# openmotestm.net
KiCad netlist of a schematic drawn in EAGLE
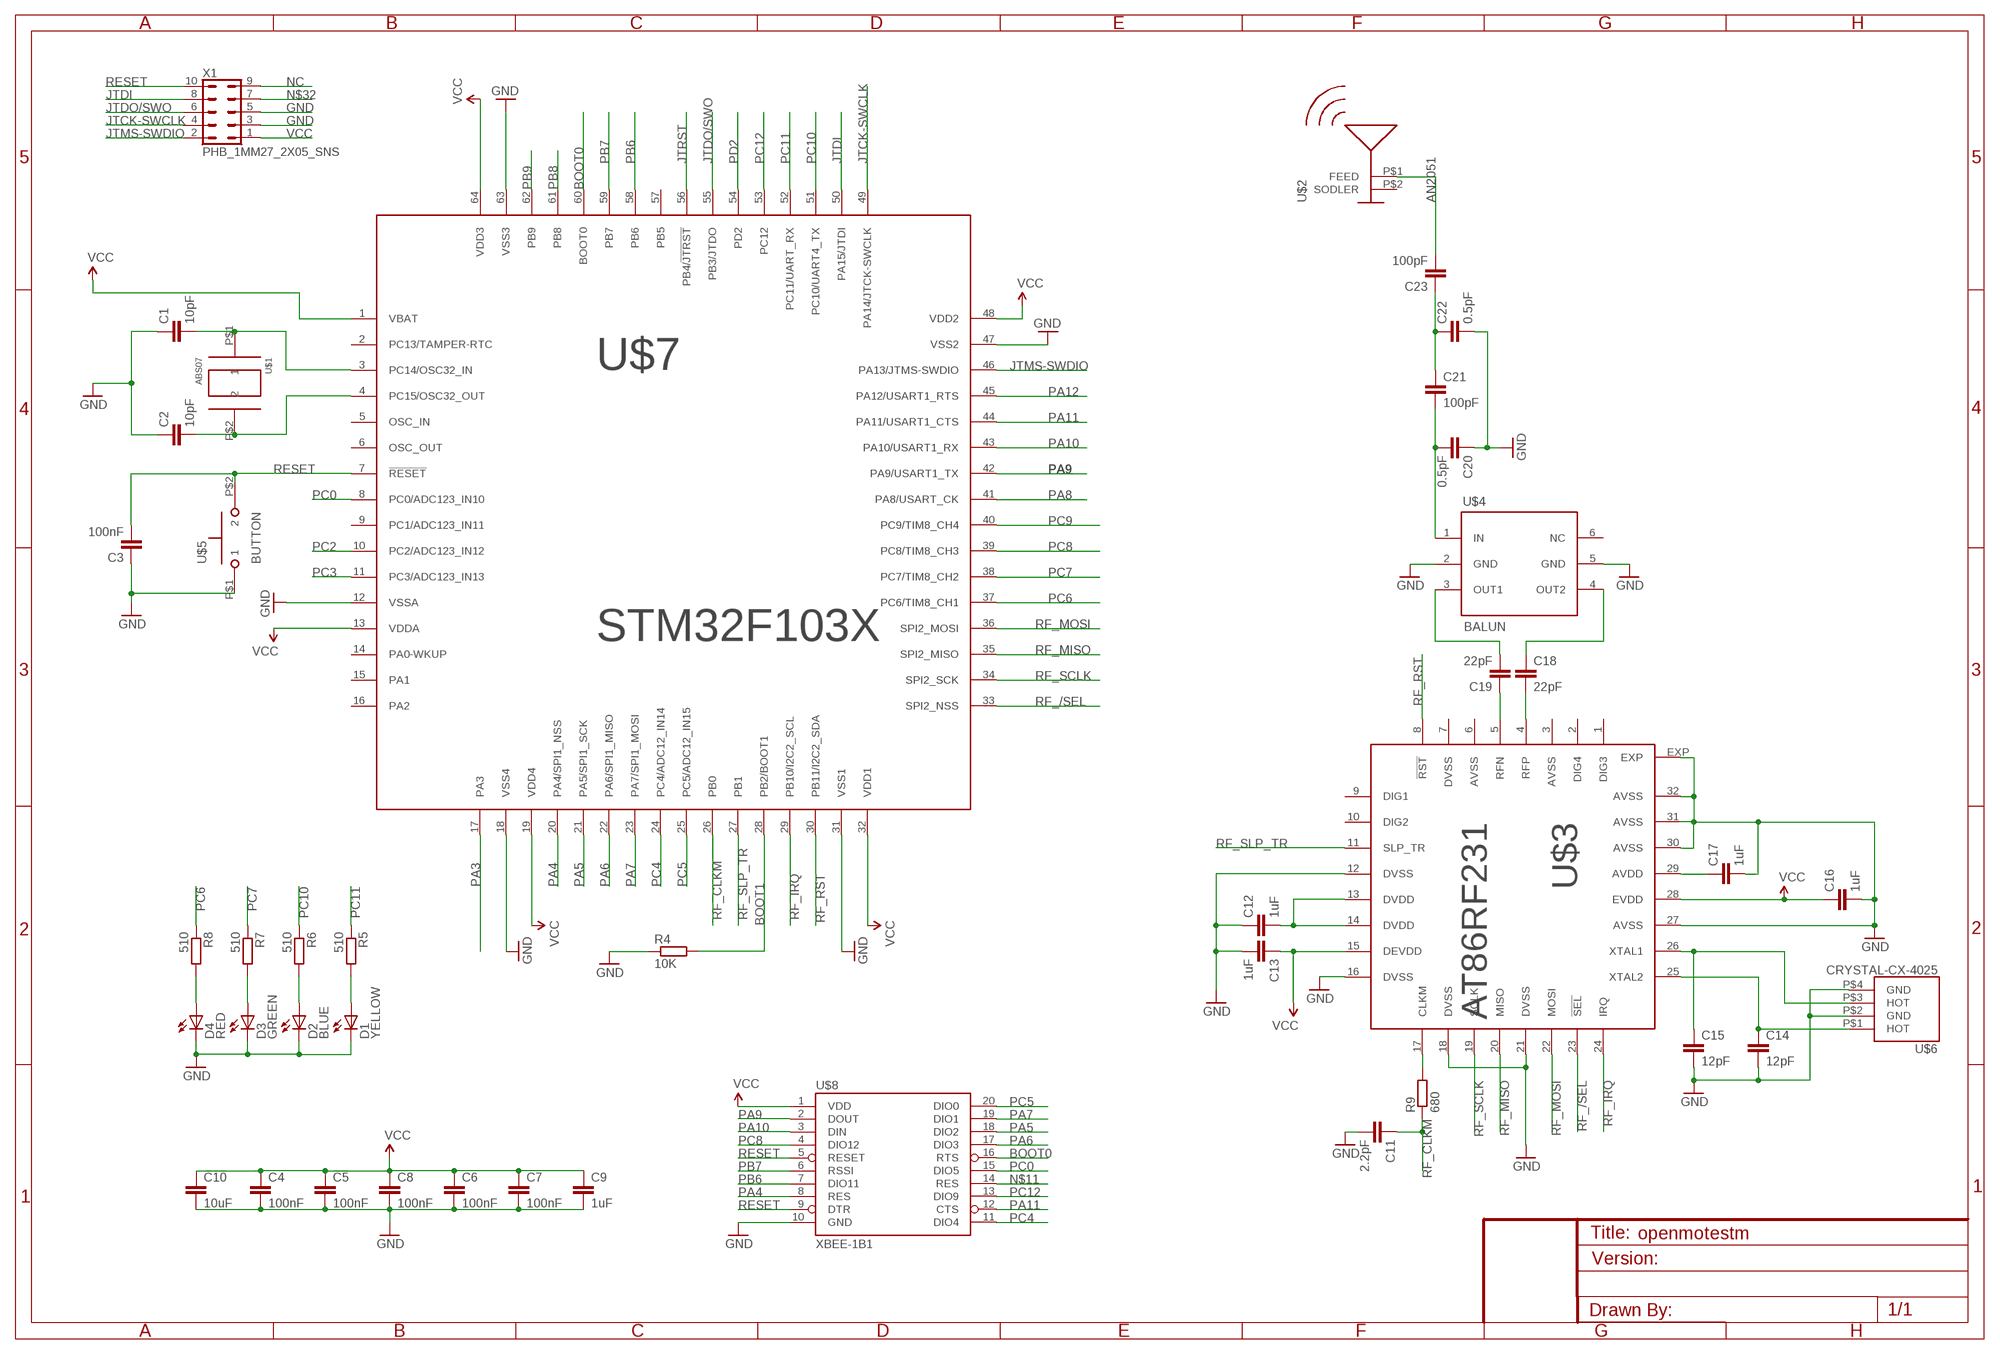
[diagram p0: schematic, sheet 1]

(export (version "E")
  (design (tool "Eeschema 10.0.6"))
  (components
    (comp (ref "C1")
      (value "10pF")
      (footprint "eagle-import:C0402")
      (libsource (lib "eagle-import") (part "resistor_C-EUC0402"))
    )
    (comp (ref "C2")
      (value "10pF")
      (footprint "eagle-import:C0402")
      (libsource (lib "eagle-import") (part "resistor_C-EUC0402"))
    )
    (comp (ref "C3")
      (value "100nF")
      (footprint "eagle-import:C0402")
      (libsource (lib "eagle-import") (part "C-EUC0402"))
    )
    (comp (ref "C4")
      (value "100nF")
      (footprint "eagle-import:C0402")
      (libsource (lib "eagle-import") (part "C-EUC0402"))
    )
    (comp (ref "C5")
      (value "100nF")
      (footprint "eagle-import:C0402")
      (libsource (lib "eagle-import") (part "C-EUC0402"))
    )
    (comp (ref "C6")
      (value "100nF")
      (footprint "eagle-import:C0402")
      (libsource (lib "eagle-import") (part "C-EUC0402"))
    )
    (comp (ref "C7")
      (value "100nF")
      (footprint "eagle-import:C0402")
      (libsource (lib "eagle-import") (part "C-EUC0402"))
    )
    (comp (ref "C8")
      (value "100nF")
      (footprint "eagle-import:C0402")
      (libsource (lib "eagle-import") (part "C-EUC0402"))
    )
    (comp (ref "C9")
      (value "1uF")
      (footprint "eagle-import:C0603")
      (libsource (lib "eagle-import") (part "C-EUC0603"))
    )
    (comp (ref "C10")
      (value "10uF")
      (footprint "eagle-import:C0603")
      (libsource (lib "eagle-import") (part "C-EUC0603"))
    )
    (comp (ref "C11")
      (value "2.2pF")
      (footprint "eagle-import:C0402")
      (libsource (lib "eagle-import") (part "C-EUC0402"))
    )
    (comp (ref "C12")
      (value "1uF")
      (footprint "eagle-import:C0603")
      (libsource (lib "eagle-import") (part "C-EUC0603"))
    )
    (comp (ref "C13")
      (value "1uF")
      (footprint "eagle-import:C0603")
      (libsource (lib "eagle-import") (part "C-EUC0603"))
    )
    (comp (ref "C14")
      (value "12pF")
      (footprint "eagle-import:C0402")
      (libsource (lib "eagle-import") (part "C-EUC0402"))
    )
    (comp (ref "C15")
      (value "12pF")
      (footprint "eagle-import:C0402")
      (libsource (lib "eagle-import") (part "C-EUC0402"))
    )
    (comp (ref "C16")
      (value "1uF")
      (footprint "eagle-import:C0603")
      (libsource (lib "eagle-import") (part "C-EUC0603"))
    )
    (comp (ref "C17")
      (value "1uF")
      (footprint "eagle-import:C0603")
      (libsource (lib "eagle-import") (part "C-EUC0603"))
    )
    (comp (ref "C18")
      (value "22pF")
      (footprint "eagle-import:C0402")
      (libsource (lib "eagle-import") (part "C-EUC0402"))
    )
    (comp (ref "C19")
      (value "22pF")
      (footprint "eagle-import:C0402")
      (libsource (lib "eagle-import") (part "C-EUC0402"))
    )
    (comp (ref "C20")
      (value "0.5pF")
      (footprint "eagle-import:C0402")
      (libsource (lib "eagle-import") (part "C-EUC0402"))
    )
    (comp (ref "C21")
      (value "100pF")
      (footprint "eagle-import:C0402")
      (libsource (lib "eagle-import") (part "C-EUC0402"))
    )
    (comp (ref "C22")
      (value "0.5pF")
      (footprint "eagle-import:C0402")
      (libsource (lib "eagle-import") (part "C-EUC0402"))
    )
    (comp (ref "C23")
      (value "100pF")
      (footprint "eagle-import:C0402")
      (libsource (lib "eagle-import") (part "C-EUC0402"))
    )
    (comp (ref "D1")
      (value "YELLOW")
      (footprint "eagle-import:LED-0603")
      (libsource (lib "eagle-import") (part "LED-YELLOW0603"))
    )
    (comp (ref "D2")
      (value "BLUE")
      (footprint "eagle-import:LED-0603")
      (libsource (lib "eagle-import") (part "LED-BLUE0603"))
    )
    (comp (ref "D3")
      (value "GREEN")
      (footprint "eagle-import:LED-0603")
      (libsource (lib "eagle-import") (part "LED-GREEN0603"))
    )
    (comp (ref "D4")
      (value "RED")
      (footprint "eagle-import:LED-0603")
      (libsource (lib "eagle-import") (part "LED-RED0603"))
    )
    (comp (ref "R4")
      (value "10K")
      (footprint "eagle-import:R0402")
      (libsource (lib "eagle-import") (part "R-EU_R0402"))
    )
    (comp (ref "R5")
      (value "510")
      (footprint "eagle-import:R0402")
      (libsource (lib "eagle-import") (part "R-EU_R0402"))
    )
    (comp (ref "R6")
      (value "510")
      (footprint "eagle-import:R0402")
      (libsource (lib "eagle-import") (part "R-EU_R0402"))
    )
    (comp (ref "R7")
      (value "510")
      (footprint "eagle-import:R0402")
      (libsource (lib "eagle-import") (part "R-EU_R0402"))
    )
    (comp (ref "R8")
      (value "510")
      (footprint "eagle-import:R0402")
      (libsource (lib "eagle-import") (part "R-EU_R0402"))
    )
    (comp (ref "R9")
      (value "680")
      (footprint "eagle-import:R0402")
      (libsource (lib "eagle-import") (part "R-EU_R0402"))
    )
    (comp (ref "U$1")
      (value "ABS07")
      (footprint "eagle-import:ABS07")
      (libsource (lib "eagle-import") (part "ABS07"))
    )
    (comp (ref "U$2")
      (value "AN2051")
      (footprint "eagle-import:AN2051")
      (libsource (lib "eagle-import") (part "AN2051"))
    )
    (comp (ref "U$3")
      (value "AT86RF231")
      (footprint "eagle-import:QFN32")
      (libsource (lib "eagle-import") (part "AT86RF231"))
    )
    (comp (ref "U$4")
      (value "BALUN")
      (footprint "eagle-import:BALUN")
      (libsource (lib "eagle-import") (part "BALUN"))
    )
    (comp (ref "U$5")
      (value "BUTTON")
      (footprint "eagle-import:BUTTON")
      (libsource (lib "eagle-import") (part "BUTTON"))
    )
    (comp (ref "U$6")
      (value "CRYSTAL-CX-4025")
      (footprint "eagle-import:CX-4025")
      (libsource (lib "eagle-import") (part "CRYSTAL-CX-4025"))
    )
    (comp (ref "U$7")
      (value "STM32F103X")
      (footprint "eagle-import:LQFP-ST-64-2")
      (libsource (lib "eagle-import") (part "STM32F103X"))
    )
    (comp (ref "U$8")
      (value "XBEE-1B1")
      (footprint "eagle-import:XBEE-1")
      (libsource (lib "eagle-import") (part "XBEE-1B1"))
    )
    (comp (ref "X1")
      (value "PHB_1MM27_2X05_SNS")
      (footprint "eagle-import:PHB_1MM27_2X05_SNS")
      (libsource (lib "eagle-import") (part "PHB_1MM27_2X05_SNS"))
    )
  )
  (nets
    (net (code "1") (name "/BOOT0") (class "Default")
      (node (ref "U$7") (pin "60") (pinfunction "BOOT0_60") (pintype "bidirectional"))
      (node (ref "U$8") (pin "16") (pinfunction "RTS_16") (pintype "input"))
    )
    (net (code "2") (name "/BOOT1") (class "Default")
      (node (ref "R4") (pin "2") (pinfunction "2_2") (pintype "passive"))
      (node (ref "U$7") (pin "28") (pinfunction "PB2/BOOT1_28") (pintype "bidirectional"))
    )
    (net (code "3") (name "/JTCK-SWCLK") (class "Default")
      (node (ref "U$7") (pin "49") (pinfunction "PA14/JTCK-SWCLK_49") (pintype "bidirectional"))
      (node (ref "X1") (pin "4") (pinfunction "4_4") (pintype "passive"))
    )
    (net (code "4") (name "/JTDI") (class "Default")
      (node (ref "U$7") (pin "50") (pinfunction "PA15/JTDI_50") (pintype "bidirectional"))
      (node (ref "X1") (pin "8") (pinfunction "8_8") (pintype "passive"))
    )
    (net (code "5") (name "/JTDO{slash}SWO") (class "Default")
      (node (ref "U$7") (pin "55") (pinfunction "PB3/JTDO_55") (pintype "bidirectional"))
      (node (ref "X1") (pin "6") (pinfunction "6_6") (pintype "passive"))
    )
    (net (code "6") (name "/JTMS-SWDIO") (class "Default")
      (node (ref "U$7") (pin "46") (pinfunction "PA13/JTMS-SWDIO_46") (pintype "bidirectional"))
      (node (ref "X1") (pin "2") (pinfunction "2_2") (pintype "passive"))
    )
    (net (code "7") (name "/JTRST") (class "Default")
      (node (ref "U$7") (pin "56") (pinfunction "PB4/~{JTRST}_56") (pintype "bidirectional"))
    )
    (net (code "8") (name "/N$11") (class "Default")
      (node (ref "U$8") (pin "14") (pinfunction "RES_14") (pintype "bidirectional"))
    )
    (net (code "9") (name "/N$32") (class "Default")
      (node (ref "X1") (pin "7") (pinfunction "7_7") (pintype "passive"))
    )
    (net (code "10") (name "/NC") (class "Default")
      (node (ref "X1") (pin "9") (pinfunction "9_9") (pintype "passive"))
    )
    (net (code "11") (name "/PA3") (class "Default")
      (node (ref "U$7") (pin "17") (pinfunction "PA3_17") (pintype "bidirectional"))
    )
    (net (code "12") (name "/PA4") (class "Default")
      (node (ref "U$7") (pin "20") (pinfunction "PA4/SPI1_NSS_20") (pintype "bidirectional"))
      (node (ref "U$8") (pin "8") (pinfunction "RES_8") (pintype "bidirectional"))
    )
    (net (code "13") (name "/PA5") (class "Default")
      (node (ref "U$7") (pin "21") (pinfunction "PA5/SPI1_SCK_21") (pintype "bidirectional"))
      (node (ref "U$8") (pin "18") (pinfunction "DIO2_18") (pintype "bidirectional"))
    )
    (net (code "14") (name "/PA6") (class "Default")
      (node (ref "U$7") (pin "22") (pinfunction "PA6/SPI1_MISO_22") (pintype "bidirectional"))
      (node (ref "U$8") (pin "17") (pinfunction "DIO3_17") (pintype "bidirectional"))
    )
    (net (code "15") (name "/PA7") (class "Default")
      (node (ref "U$7") (pin "23") (pinfunction "PA7/SPI1_MOSI_23") (pintype "bidirectional"))
      (node (ref "U$8") (pin "19") (pinfunction "DIO1_19") (pintype "bidirectional"))
    )
    (net (code "16") (name "/PA8") (class "Default")
      (node (ref "U$7") (pin "41") (pinfunction "PA8/USART_CK_41") (pintype "bidirectional"))
    )
    (net (code "17") (name "/PA9") (class "Default")
      (node (ref "U$7") (pin "42") (pinfunction "PA9/USART1_TX_42") (pintype "bidirectional"))
      (node (ref "U$8") (pin "2") (pinfunction "DOUT_2") (pintype "output"))
    )
    (net (code "18") (name "/PA10") (class "Default")
      (node (ref "U$7") (pin "43") (pinfunction "PA10/USART1_RX_43") (pintype "bidirectional"))
      (node (ref "U$8") (pin "3") (pinfunction "DIN_3") (pintype "input"))
    )
    (net (code "19") (name "/PA11") (class "Default")
      (node (ref "U$7") (pin "44") (pinfunction "PA11/USART1_CTS_44") (pintype "bidirectional"))
      (node (ref "U$8") (pin "12") (pinfunction "CTS_12") (pintype "output"))
    )
    (net (code "20") (name "/PA12") (class "Default")
      (node (ref "U$7") (pin "45") (pinfunction "PA12/USART1_RTS_45") (pintype "bidirectional"))
    )
    (net (code "21") (name "/PB6") (class "Default")
      (node (ref "U$7") (pin "58") (pinfunction "PB6_58") (pintype "bidirectional"))
      (node (ref "U$8") (pin "7") (pinfunction "DIO11_7") (pintype "bidirectional"))
    )
    (net (code "22") (name "/PB7") (class "Default")
      (node (ref "U$7") (pin "59") (pinfunction "PB7_59") (pintype "bidirectional"))
      (node (ref "U$8") (pin "6") (pinfunction "RSSI_6") (pintype "bidirectional"))
    )
    (net (code "23") (name "/PB8") (class "Default")
      (node (ref "U$7") (pin "61") (pinfunction "PB8_61") (pintype "bidirectional"))
    )
    (net (code "24") (name "/PB9") (class "Default")
      (node (ref "U$7") (pin "62") (pinfunction "PB9_62") (pintype "bidirectional"))
    )
    (net (code "25") (name "/PC0") (class "Default")
      (node (ref "U$7") (pin "8") (pinfunction "PC0/ADC123_IN10_8") (pintype "bidirectional"))
      (node (ref "U$8") (pin "15") (pinfunction "DIO5_15") (pintype "bidirectional"))
    )
    (net (code "26") (name "/PC2") (class "Default")
      (node (ref "U$7") (pin "10") (pinfunction "PC2/ADC123_IN12_10") (pintype "bidirectional"))
    )
    (net (code "27") (name "/PC3") (class "Default")
      (node (ref "U$7") (pin "11") (pinfunction "PC3/ADC123_IN13_11") (pintype "bidirectional"))
    )
    (net (code "28") (name "/PC4") (class "Default")
      (node (ref "U$7") (pin "24") (pinfunction "PC4/ADC12_IN14_24") (pintype "bidirectional"))
      (node (ref "U$8") (pin "11") (pinfunction "DIO4_11") (pintype "bidirectional"))
    )
    (net (code "29") (name "/PC5") (class "Default")
      (node (ref "U$7") (pin "25") (pinfunction "PC5/ADC12_IN15_25") (pintype "bidirectional"))
      (node (ref "U$8") (pin "20") (pinfunction "DIO0_20") (pintype "bidirectional"))
    )
    (net (code "30") (name "/PC6") (class "Default")
      (node (ref "R8") (pin "1") (pinfunction "1_1") (pintype "passive"))
      (node (ref "U$7") (pin "37") (pinfunction "PC6/TIM8_CH1_37") (pintype "bidirectional"))
    )
    (net (code "31") (name "/PC7") (class "Default")
      (node (ref "R7") (pin "1") (pinfunction "1_1") (pintype "passive"))
      (node (ref "U$7") (pin "38") (pinfunction "PC7/TIM8_CH2_38") (pintype "bidirectional"))
    )
    (net (code "32") (name "/PC8") (class "Default")
      (node (ref "U$7") (pin "39") (pinfunction "PC8/TIM8_CH3_39") (pintype "bidirectional"))
      (node (ref "U$8") (pin "4") (pinfunction "DIO12_4") (pintype "bidirectional"))
    )
    (net (code "33") (name "/PC9") (class "Default")
      (node (ref "U$7") (pin "40") (pinfunction "PC9/TIM8_CH4_40") (pintype "output"))
    )
    (net (code "34") (name "/PC10") (class "Default")
      (node (ref "R6") (pin "1") (pinfunction "1_1") (pintype "passive"))
      (node (ref "U$7") (pin "51") (pinfunction "PC10/UART4_TX_51") (pintype "bidirectional"))
    )
    (net (code "35") (name "/PC11") (class "Default")
      (node (ref "R5") (pin "1") (pinfunction "1_1") (pintype "passive"))
      (node (ref "U$7") (pin "52") (pinfunction "PC11/UART_RX_52") (pintype "bidirectional"))
    )
    (net (code "36") (name "/PC12") (class "Default")
      (node (ref "U$7") (pin "53") (pinfunction "PC12_53") (pintype "bidirectional"))
      (node (ref "U$8") (pin "13") (pinfunction "DIO9_13") (pintype "bidirectional"))
    )
    (net (code "37") (name "/PD2") (class "Default")
      (node (ref "U$7") (pin "54") (pinfunction "PD2_54") (pintype "bidirectional"))
    )
    (net (code "38") (name "/RESET") (class "Default")
      (node (ref "C3") (pin "2") (pinfunction "2_2") (pintype "passive"))
      (node (ref "U$5") (pin "P$2") (pinfunction "2_P$2") (pintype "bidirectional"))
      (node (ref "U$7") (pin "7") (pinfunction "~{RESET}_7") (pintype "output"))
      (node (ref "U$8") (pin "5") (pinfunction "RESET_5") (pintype "input"))
      (node (ref "U$8") (pin "9") (pinfunction "DTR_9") (pintype "bidirectional"))
      (node (ref "X1") (pin "10") (pinfunction "10_10") (pintype "passive"))
    )
    (net (code "39") (name "/RF_CLKM") (class "Default")
      (node (ref "C11") (pin "1") (pinfunction "1_1") (pintype "passive"))
      (node (ref "R9") (pin "1") (pinfunction "1_1") (pintype "passive"))
      (node (ref "U$7") (pin "26") (pinfunction "PB0_26") (pintype "bidirectional"))
    )
    (net (code "40") (name "/RF_IRQ") (class "Default")
      (node (ref "U$3") (pin "24") (pinfunction "IRQ_24") (pintype "bidirectional"))
      (node (ref "U$7") (pin "29") (pinfunction "PB10/I2C2_SCL_29") (pintype "bidirectional"))
    )
    (net (code "41") (name "/RF_MISO") (class "Default")
      (node (ref "U$3") (pin "20") (pinfunction "MISO_20") (pintype "bidirectional"))
      (node (ref "U$7") (pin "35") (pinfunction "SPI2_MISO_35") (pintype "bidirectional"))
    )
    (net (code "42") (name "/RF_MOSI") (class "Default")
      (node (ref "U$3") (pin "22") (pinfunction "MOSI_22") (pintype "bidirectional"))
      (node (ref "U$7") (pin "36") (pinfunction "SPI2_MOSI_36") (pintype "bidirectional"))
    )
    (net (code "43") (name "/RF_RST") (class "Default")
      (node (ref "U$3") (pin "8") (pinfunction "~{RST}_8") (pintype "bidirectional"))
      (node (ref "U$7") (pin "30") (pinfunction "PB11/I2C2_SDA_30") (pintype "bidirectional"))
    )
    (net (code "44") (name "/RF_SCLK") (class "Default")
      (node (ref "U$3") (pin "19") (pinfunction "SCLK_19") (pintype "bidirectional"))
      (node (ref "U$7") (pin "34") (pinfunction "SPI2_SCK_34") (pintype "bidirectional"))
    )
    (net (code "45") (name "/RF_SLP_TR") (class "Default")
      (node (ref "U$3") (pin "11") (pinfunction "SLP_TR_11") (pintype "bidirectional"))
      (node (ref "U$7") (pin "27") (pinfunction "PB1_27") (pintype "bidirectional"))
    )
    (net (code "46") (name "/RF_{slash}SEL") (class "Default")
      (node (ref "U$3") (pin "23") (pinfunction "~{SEL}_23") (pintype "bidirectional"))
      (node (ref "U$7") (pin "33") (pinfunction "SPI2_NSS_33") (pintype "bidirectional"))
    )
    (net (code "47") (name "GND") (class "Default")
      (node (ref "C1") (pin "1") (pinfunction "1_1") (pintype "passive"))
      (node (ref "C10") (pin "2") (pinfunction "2_2") (pintype "passive"))
      (node (ref "C11") (pin "2") (pinfunction "2_2") (pintype "passive"))
      (node (ref "C12") (pin "1") (pinfunction "1_1") (pintype "passive"))
      (node (ref "C13") (pin "2") (pinfunction "2_2") (pintype "passive"))
      (node (ref "C14") (pin "2") (pinfunction "2_2") (pintype "passive"))
      (node (ref "C15") (pin "2") (pinfunction "2_2") (pintype "passive"))
      (node (ref "C16") (pin "2") (pinfunction "2_2") (pintype "passive"))
      (node (ref "C17") (pin "2") (pinfunction "2_2") (pintype "passive"))
      (node (ref "C2") (pin "1") (pinfunction "1_1") (pintype "passive"))
      (node (ref "C20") (pin "1") (pinfunction "1_1") (pintype "passive"))
      (node (ref "C22") (pin "2") (pinfunction "2_2") (pintype "passive"))
      (node (ref "C3") (pin "1") (pinfunction "1_1") (pintype "passive"))
      (node (ref "C4") (pin "2") (pinfunction "2_2") (pintype "passive"))
      (node (ref "C5") (pin "2") (pinfunction "2_2") (pintype "passive"))
      (node (ref "C6") (pin "2") (pinfunction "2_2") (pintype "passive"))
      (node (ref "C7") (pin "2") (pinfunction "2_2") (pintype "passive"))
      (node (ref "C8") (pin "2") (pinfunction "2_2") (pintype "passive"))
      (node (ref "C9") (pin "2") (pinfunction "2_2") (pintype "passive"))
      (node (ref "D1") (pin "C") (pinfunction "C_C") (pintype "passive"))
      (node (ref "D2") (pin "C") (pinfunction "C_C") (pintype "passive"))
      (node (ref "D3") (pin "C") (pinfunction "C_C") (pintype "passive"))
      (node (ref "D4") (pin "C") (pinfunction "C_C") (pintype "passive"))
      (node (ref "R4") (pin "1") (pinfunction "1_1") (pintype "passive"))
      (node (ref "U$3") (pin "12") (pinfunction "DVSS_12") (pintype "bidirectional"))
      (node (ref "U$3") (pin "16") (pinfunction "DVSS_16") (pintype "bidirectional"))
      (node (ref "U$3") (pin "18") (pinfunction "DVSS_18") (pintype "bidirectional"))
      (node (ref "U$3") (pin "21") (pinfunction "DVSS_21") (pintype "bidirectional"))
      (node (ref "U$3") (pin "27") (pinfunction "AVSS_27") (pintype "bidirectional"))
      (node (ref "U$3") (pin "30") (pinfunction "AVSS_30") (pintype "bidirectional"))
      (node (ref "U$3") (pin "31") (pinfunction "AVSS_31") (pintype "bidirectional"))
      (node (ref "U$3") (pin "32") (pinfunction "AVSS_32") (pintype "bidirectional"))
      (node (ref "U$3") (pin "EXP") (pinfunction "EXP_EXP") (pintype "bidirectional"))
      (node (ref "U$4") (pin "2") (pinfunction "GND_2") (pintype "power_in"))
      (node (ref "U$4") (pin "5") (pinfunction "GND_5") (pintype "power_in"))
      (node (ref "U$5") (pin "P$1") (pinfunction "1_P$1") (pintype "bidirectional"))
      (node (ref "U$6") (pin "P$2") (pinfunction "GND_P$2") (pintype "power_in"))
      (node (ref "U$6") (pin "P$4") (pinfunction "GND_P$4") (pintype "power_in"))
      (node (ref "U$7") (pin "12") (pinfunction "VSSA_12") (pintype "power_in"))
      (node (ref "U$7") (pin "18") (pinfunction "VSS4_18") (pintype "power_in"))
      (node (ref "U$7") (pin "31") (pinfunction "VSS1_31") (pintype "power_in"))
      (node (ref "U$7") (pin "47") (pinfunction "VSS2_47") (pintype "power_in"))
      (node (ref "U$7") (pin "63") (pinfunction "VSS3_63") (pintype "power_in"))
      (node (ref "U$8") (pin "10") (pinfunction "GND_10") (pintype "power_in"))
      (node (ref "X1") (pin "3") (pinfunction "3_3") (pintype "passive"))
      (node (ref "X1") (pin "5") (pinfunction "5_5") (pintype "passive"))
    )
    (net (code "48") (name "Net-(C12-Pad2)") (class "Default")
      (node (ref "C12") (pin "2") (pinfunction "2_2") (pintype "passive"))
      (node (ref "U$3") (pin "13") (pinfunction "DVDD_13") (pintype "bidirectional"))
      (node (ref "U$3") (pin "14") (pinfunction "DVDD_14") (pintype "bidirectional"))
    )
    (net (code "49") (name "Net-(C21-Pad1)") (class "Default")
      (node (ref "C21") (pin "1") (pinfunction "1_1") (pintype "passive"))
      (node (ref "C22") (pin "1") (pinfunction "1_1") (pintype "passive"))
      (node (ref "C23") (pin "1") (pinfunction "1_1") (pintype "passive"))
    )
    (net (code "50") (name "Net-(D1-PadA)") (class "Default")
      (node (ref "D1") (pin "A") (pinfunction "A_A") (pintype "passive"))
      (node (ref "R5") (pin "2") (pinfunction "2_2") (pintype "passive"))
    )
    (net (code "51") (name "Net-(D2-PadA)") (class "Default")
      (node (ref "D2") (pin "A") (pinfunction "A_A") (pintype "passive"))
      (node (ref "R6") (pin "2") (pinfunction "2_2") (pintype "passive"))
    )
    (net (code "52") (name "Net-(D3-PadA)") (class "Default")
      (node (ref "D3") (pin "A") (pinfunction "A_A") (pintype "passive"))
      (node (ref "R7") (pin "2") (pinfunction "2_2") (pintype "passive"))
    )
    (net (code "53") (name "Net-(D4-PadA)") (class "Default")
      (node (ref "D4") (pin "A") (pinfunction "A_A") (pintype "passive"))
      (node (ref "R8") (pin "2") (pinfunction "2_2") (pintype "passive"))
    )
    (net (code "54") (name "Net-(U$1-1)") (class "Default")
      (node (ref "C1") (pin "2") (pinfunction "2_2") (pintype "passive"))
      (node (ref "U$1") (pin "P$1") (pinfunction "1_P$1") (pintype "bidirectional"))
      (node (ref "U$7") (pin "3") (pinfunction "PC14/OSC32_IN_3") (pintype "bidirectional"))
    )
    (net (code "55") (name "Net-(U$1-2)") (class "Default")
      (node (ref "C2") (pin "2") (pinfunction "2_2") (pintype "passive"))
      (node (ref "U$1") (pin "P$2") (pinfunction "2_P$2") (pintype "bidirectional"))
      (node (ref "U$7") (pin "4") (pinfunction "PC15/OSC32_OUT_4") (pintype "bidirectional"))
    )
    (net (code "56") (name "Net-(U$2-FEED)") (class "Default")
      (node (ref "C23") (pin "2") (pinfunction "2_2") (pintype "passive"))
      (node (ref "U$2") (pin "P$1") (pinfunction "FEED_P$1") (pintype "bidirectional"))
    )
    (net (code "57") (name "Net-(U$3-AVDD)") (class "Default")
      (node (ref "C17") (pin "1") (pinfunction "1_1") (pintype "passive"))
      (node (ref "U$3") (pin "29") (pinfunction "AVDD_29") (pintype "bidirectional"))
    )
    (net (code "58") (name "Net-(U$3-CLKM)") (class "Default")
      (node (ref "R9") (pin "2") (pinfunction "2_2") (pintype "passive"))
      (node (ref "U$3") (pin "17") (pinfunction "CLKM_17") (pintype "bidirectional"))
    )
    (net (code "59") (name "Net-(U$3-RFN)") (class "Default")
      (node (ref "C19") (pin "1") (pinfunction "1_1") (pintype "passive"))
      (node (ref "U$3") (pin "5") (pinfunction "RFN_5") (pintype "bidirectional"))
    )
    (net (code "60") (name "Net-(U$3-RFP)") (class "Default")
      (node (ref "C18") (pin "2") (pinfunction "2_2") (pintype "passive"))
      (node (ref "U$3") (pin "4") (pinfunction "RFP_4") (pintype "bidirectional"))
    )
    (net (code "61") (name "Net-(U$3-XTAL1)") (class "Default")
      (node (ref "C15") (pin "1") (pinfunction "1_1") (pintype "passive"))
      (node (ref "U$3") (pin "26") (pinfunction "XTAL1_26") (pintype "bidirectional"))
      (node (ref "U$6") (pin "P$3") (pinfunction "HOT_P$3") (pintype "bidirectional"))
    )
    (net (code "62") (name "Net-(U$3-XTAL2)") (class "Default")
      (node (ref "C14") (pin "1") (pinfunction "1_1") (pintype "passive"))
      (node (ref "U$3") (pin "25") (pinfunction "XTAL2_25") (pintype "bidirectional"))
      (node (ref "U$6") (pin "P$1") (pinfunction "HOT_P$1") (pintype "bidirectional"))
    )
    (net (code "63") (name "Net-(U$4-IN)") (class "Default")
      (node (ref "C20") (pin "2") (pinfunction "2_2") (pintype "passive"))
      (node (ref "C21") (pin "2") (pinfunction "2_2") (pintype "passive"))
      (node (ref "U$4") (pin "1") (pinfunction "IN_1") (pintype "bidirectional"))
    )
    (net (code "64") (name "Net-(U$4-OUT1)") (class "Default")
      (node (ref "C19") (pin "2") (pinfunction "2_2") (pintype "passive"))
      (node (ref "U$4") (pin "3") (pinfunction "OUT1_3") (pintype "bidirectional"))
    )
    (net (code "65") (name "Net-(U$4-OUT2)") (class "Default")
      (node (ref "C18") (pin "1") (pinfunction "1_1") (pintype "passive"))
      (node (ref "U$4") (pin "4") (pinfunction "OUT2_4") (pintype "bidirectional"))
    )
    (net (code "66") (name "VCC") (class "Default")
      (node (ref "C10") (pin "1") (pinfunction "1_1") (pintype "passive"))
      (node (ref "C13") (pin "1") (pinfunction "1_1") (pintype "passive"))
      (node (ref "C16") (pin "1") (pinfunction "1_1") (pintype "passive"))
      (node (ref "C4") (pin "1") (pinfunction "1_1") (pintype "passive"))
      (node (ref "C5") (pin "1") (pinfunction "1_1") (pintype "passive"))
      (node (ref "C6") (pin "1") (pinfunction "1_1") (pintype "passive"))
      (node (ref "C7") (pin "1") (pinfunction "1_1") (pintype "passive"))
      (node (ref "C8") (pin "1") (pinfunction "1_1") (pintype "passive"))
      (node (ref "C9") (pin "1") (pinfunction "1_1") (pintype "passive"))
      (node (ref "U$3") (pin "15") (pinfunction "DEVDD_15") (pintype "bidirectional"))
      (node (ref "U$3") (pin "28") (pinfunction "EVDD_28") (pintype "bidirectional"))
      (node (ref "U$7") (pin "1") (pinfunction "VBAT_1") (pintype "power_in"))
      (node (ref "U$7") (pin "13") (pinfunction "VDDA_13") (pintype "power_in"))
      (node (ref "U$7") (pin "19") (pinfunction "VDD4_19") (pintype "power_in"))
      (node (ref "U$7") (pin "32") (pinfunction "VDD1_32") (pintype "power_in"))
      (node (ref "U$7") (pin "48") (pinfunction "VDD2_48") (pintype "power_in"))
      (node (ref "U$7") (pin "64") (pinfunction "VDD3_64") (pintype "power_in"))
      (node (ref "U$8") (pin "1") (pinfunction "VDD_1") (pintype "power_in"))
      (node (ref "X1") (pin "1") (pinfunction "1_1") (pintype "passive"))
    )
    (net (code "67") (name "unconnected-(U$2-SODLER-PadP$2)") (class "Default")
      (node (ref "U$2") (pin "P$2") (pinfunction "SODLER_P$2") (pintype "bidirectional"))
    )
    (net (code "68") (name "unconnected-(U$3-AVSS-Pad3)") (class "Default")
      (node (ref "U$3") (pin "3") (pinfunction "AVSS_3") (pintype "bidirectional"))
    )
    (net (code "69") (name "unconnected-(U$3-AVSS-Pad6)") (class "Default")
      (node (ref "U$3") (pin "6") (pinfunction "AVSS_6") (pintype "bidirectional"))
    )
    (net (code "70") (name "unconnected-(U$3-DIG1-Pad9)") (class "Default")
      (node (ref "U$3") (pin "9") (pinfunction "DIG1_9") (pintype "bidirectional"))
    )
    (net (code "71") (name "unconnected-(U$3-DIG2-Pad10)") (class "Default")
      (node (ref "U$3") (pin "10") (pinfunction "DIG2_10") (pintype "bidirectional"))
    )
    (net (code "72") (name "unconnected-(U$3-DIG3-Pad1)") (class "Default")
      (node (ref "U$3") (pin "1") (pinfunction "DIG3_1") (pintype "bidirectional"))
    )
    (net (code "73") (name "unconnected-(U$3-DIG4-Pad2)") (class "Default")
      (node (ref "U$3") (pin "2") (pinfunction "DIG4_2") (pintype "bidirectional"))
    )
    (net (code "74") (name "unconnected-(U$3-DVSS-Pad7)") (class "Default")
      (node (ref "U$3") (pin "7") (pinfunction "DVSS_7") (pintype "bidirectional"))
    )
    (net (code "75") (name "unconnected-(U$4-NC-Pad6)") (class "Default")
      (node (ref "U$4") (pin "6") (pinfunction "NC_6") (pintype "bidirectional"))
    )
    (net (code "76") (name "unconnected-(U$7-OSC_IN-Pad5)") (class "Default")
      (node (ref "U$7") (pin "5") (pinfunction "OSC_IN_5") (pintype "bidirectional"))
    )
    (net (code "77") (name "unconnected-(U$7-OSC_OUT-Pad6)") (class "Default")
      (node (ref "U$7") (pin "6") (pinfunction "OSC_OUT_6") (pintype "bidirectional"))
    )
    (net (code "78") (name "unconnected-(U$7-PA0-WKUP-Pad14)") (class "Default")
      (node (ref "U$7") (pin "14") (pinfunction "PA0-WKUP_14") (pintype "bidirectional"))
    )
    (net (code "79") (name "unconnected-(U$7-PA1-Pad15)") (class "Default")
      (node (ref "U$7") (pin "15") (pinfunction "PA1_15") (pintype "bidirectional"))
    )
    (net (code "80") (name "unconnected-(U$7-PA2-Pad16)") (class "Default")
      (node (ref "U$7") (pin "16") (pinfunction "PA2_16") (pintype "bidirectional"))
    )
    (net (code "81") (name "unconnected-(U$7-PB5-Pad57)") (class "Default")
      (node (ref "U$7") (pin "57") (pinfunction "PB5_57") (pintype "bidirectional"))
    )
    (net (code "82") (name "unconnected-(U$7-PC1{slash}ADC123_IN11-Pad9)") (class "Default")
      (node (ref "U$7") (pin "9") (pinfunction "PC1/ADC123_IN11_9") (pintype "output"))
    )
    (net (code "83") (name "unconnected-(U$7-PC13{slash}TAMPER-RTC-Pad2)") (class "Default")
      (node (ref "U$7") (pin "2") (pinfunction "PC13/TAMPER-RTC_2") (pintype "bidirectional"))
    )
  )
)
